# low_pass_filter.net
KiCad netlist of a schematic drawn in Altium Designer
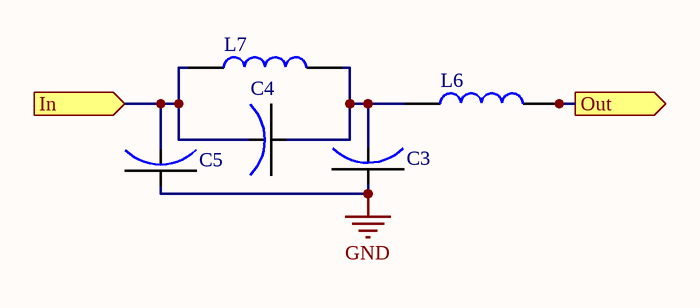
[diagram p0: low_pass_filter.SchDoc]

(export (version "E")
  (design (tool "Eeschema 10.0.6"))
  (components
    (comp (ref "C3") (value "Cap") (footprint "C1206") (libsource (lib "Integrated_Library1") (part "Cap")))
    (comp (ref "C4") (value "Cap") (footprint "C1812") (libsource (lib "Integrated_Library1") (part "Cap")))
    (comp (ref "C5") (value "Cap") (footprint "C1812") (libsource (lib "Integrated_Library1") (part "Cap")))
    (comp (ref "L6")
      (value "L1812")
      (footprint "L1812")
      (description "Vishay IMC1812ER150J")
      (libsource (lib "Integrated_Library1") (part "L1812"))
    )
    (comp (ref "L7")
      (value "L1812")
      (footprint "L1812")
      (description "Vishay IMC1812ER150J")
      (libsource (lib "Integrated_Library1") (part "L1812"))
    )
  )
  (nets
    (net (code "1") (name "/In") (class "Default")
      (node (ref "C4") (pin "1") (pinfunction "1_1") (pintype "passive"))
      (node (ref "C5") (pin "1") (pinfunction "1_1") (pintype "passive"))
      (node (ref "L7") (pin "1") (pinfunction "1_1") (pintype "passive"))
    )
    (net (code "2") (name "/Out") (class "Default")
      (node (ref "L6") (pin "2") (pinfunction "2_2") (pintype "passive"))
    )
    (net (code "3") (name "GND") (class "Default")
      (node (ref "C3") (pin "2") (pinfunction "2_2") (pintype "passive"))
      (node (ref "C5") (pin "2") (pinfunction "2_2") (pintype "passive"))
    )
    (net (code "4") (name "Net-(C3-Pad1)") (class "Default")
      (node (ref "C3") (pin "1") (pinfunction "1_1") (pintype "passive"))
      (node (ref "C4") (pin "2") (pinfunction "2_2") (pintype "passive"))
      (node (ref "L6") (pin "1") (pinfunction "1_1") (pintype "passive"))
      (node (ref "L7") (pin "2") (pinfunction "2_2") (pintype "passive"))
    )
  )
)
